# box.net
KiCad netlist of a schematic drawn in EAGLE
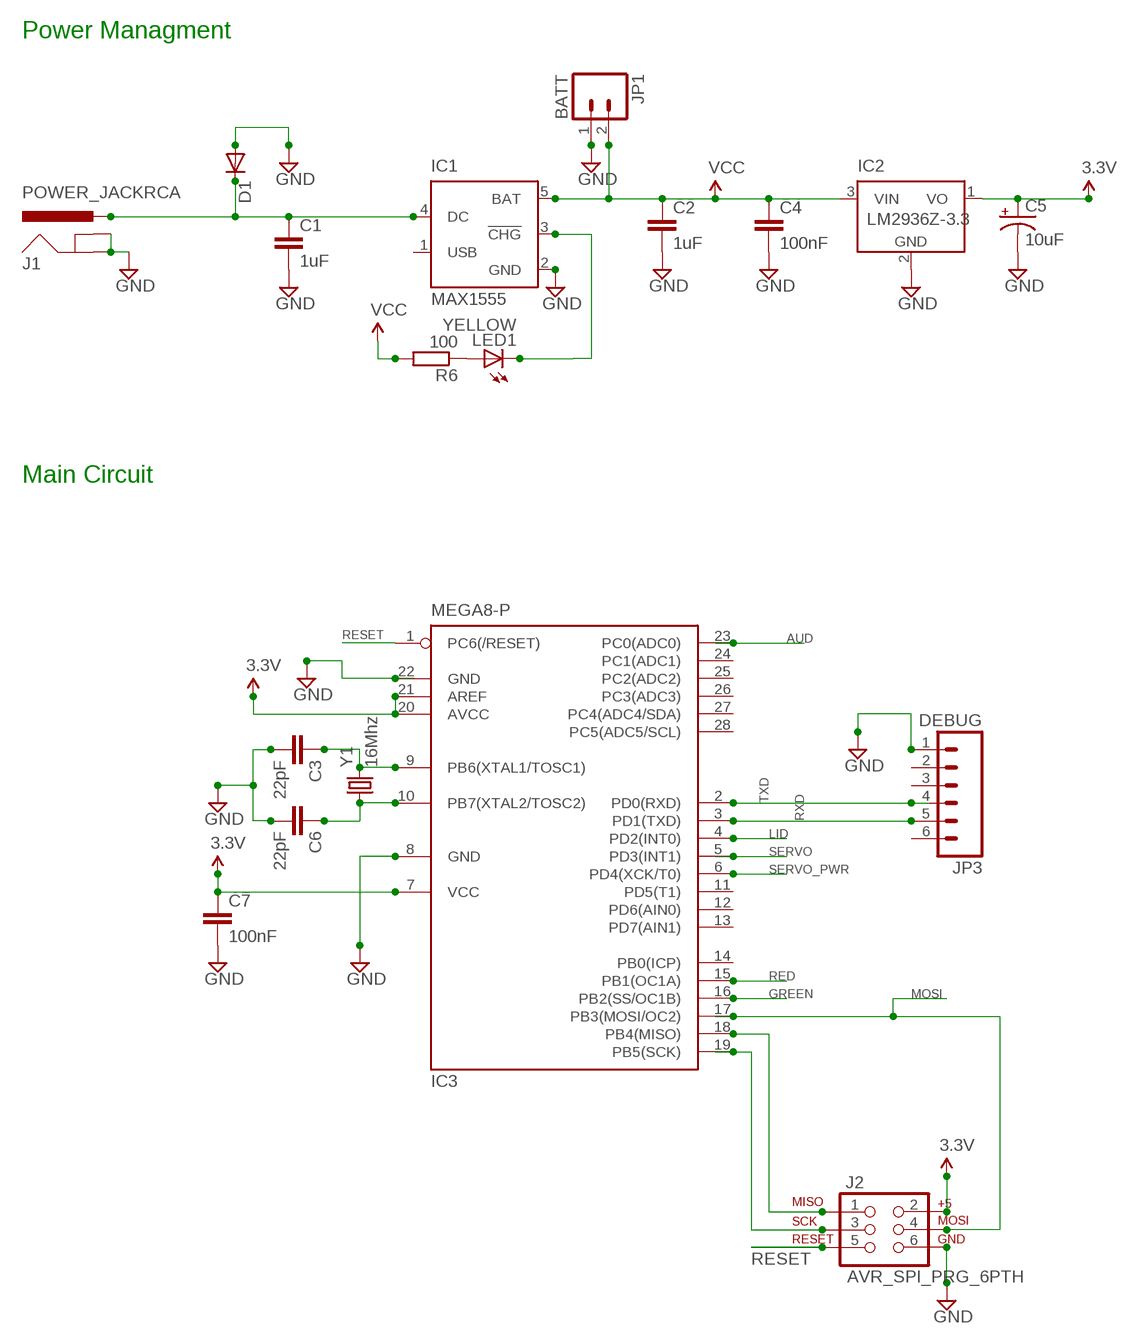
[diagram p0: schematic, sheet 1, part 1 of 2]
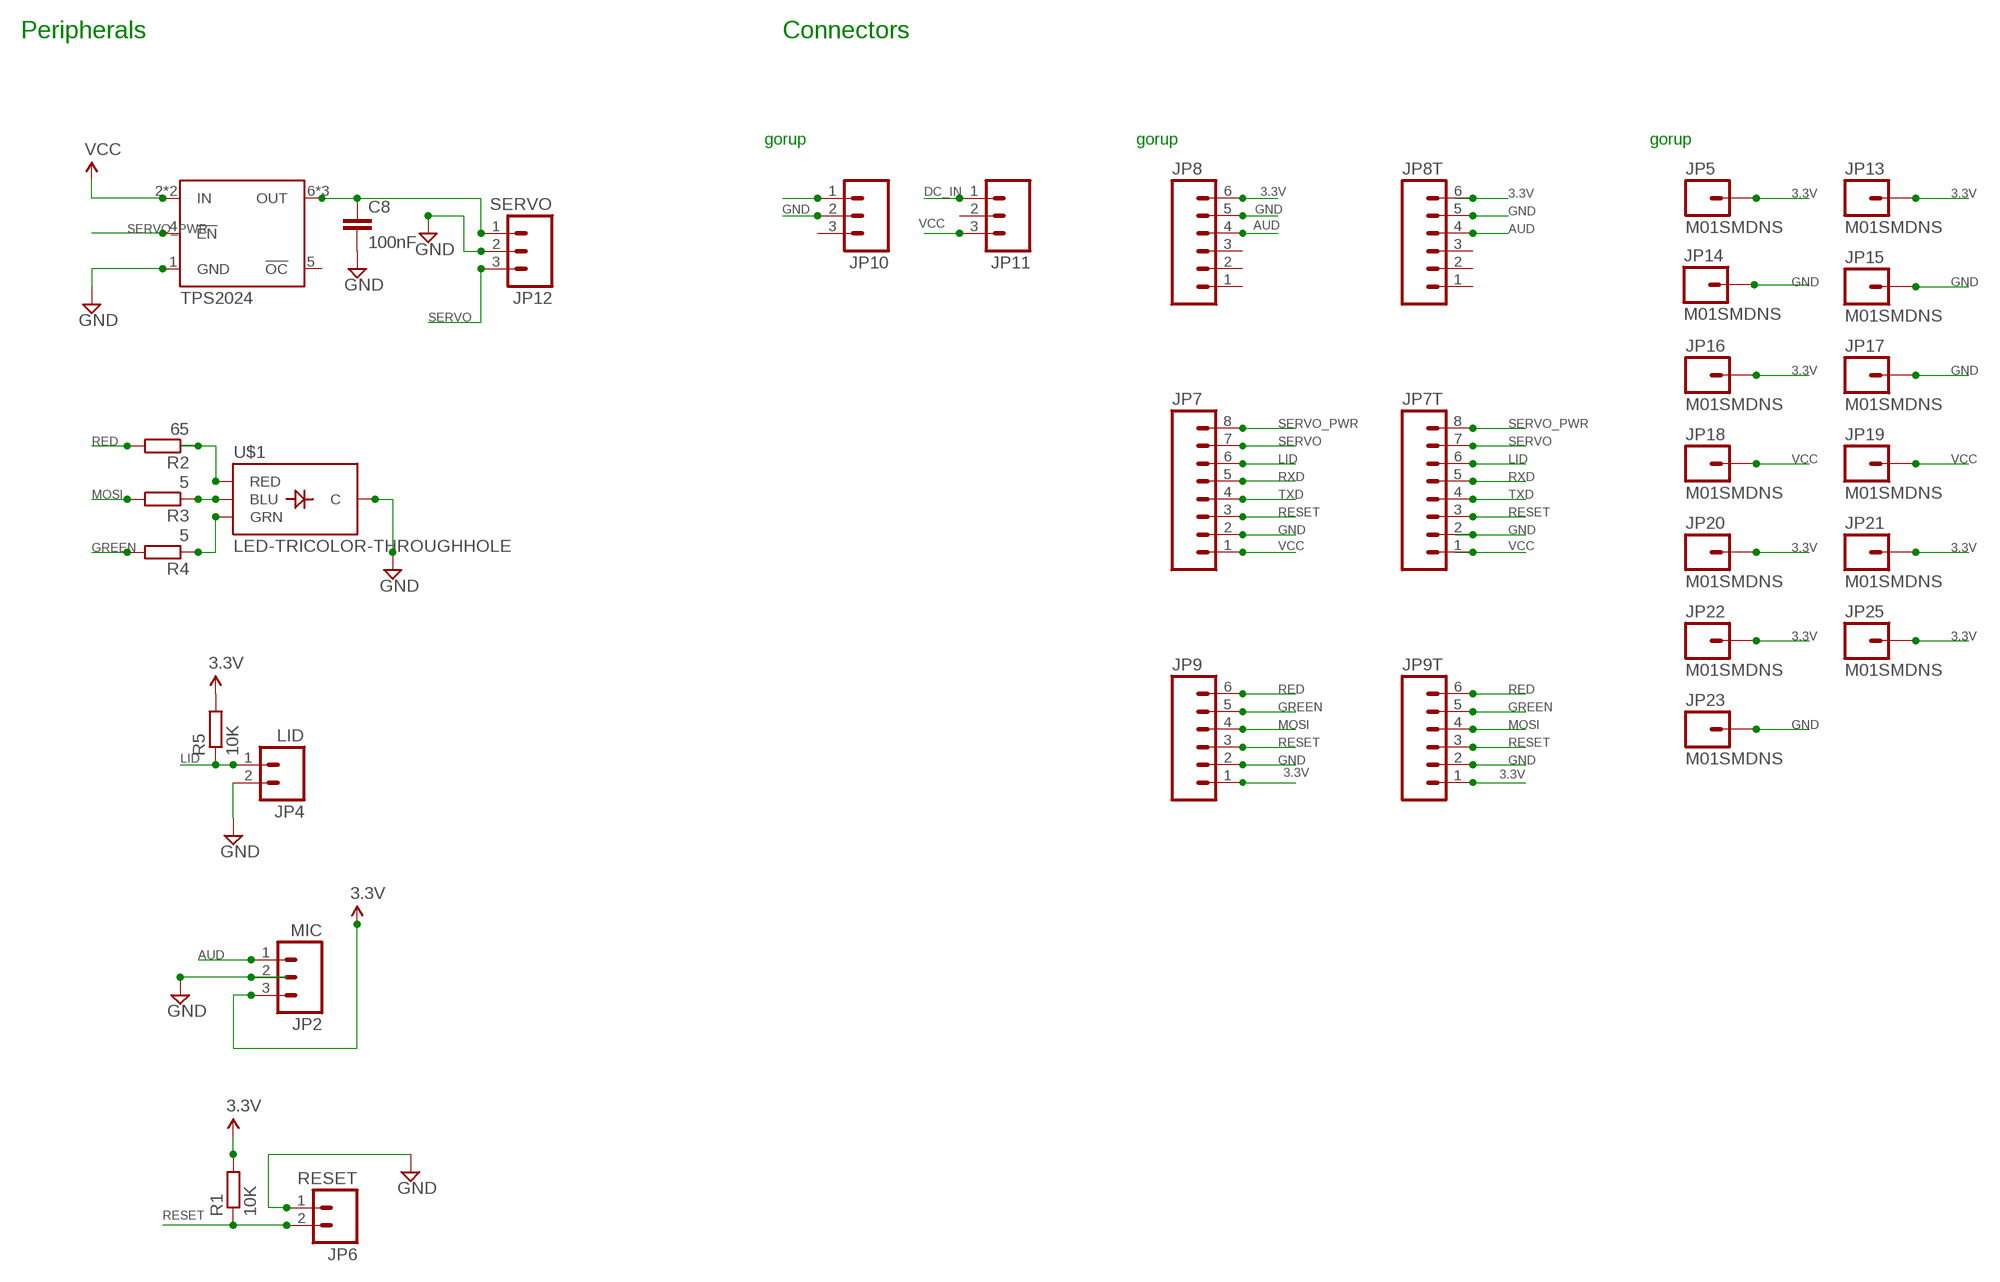
[diagram p1: schematic, sheet 1, part 2 of 2]

(export (version "E")
  (design (tool "Eeschema 10.0.6"))
  (components
    (comp (ref "C1")
      (value "1uF")
      (footprint "eagle-import:AXIAL-5MM")
      (libsource (lib "eagle-import") (part "CAP_"))
    )
    (comp (ref "C2")
      (value "1uF")
      (footprint "eagle-import:AXIAL-5MM")
      (libsource (lib "eagle-import") (part "CAP_"))
    )
    (comp (ref "C3")
      (value "22pF")
      (footprint "eagle-import:C2.5-2")
      (libsource (lib "eagle-import") (part "C2.5/2"))
    )
    (comp (ref "C4")
      (value "100nF")
      (footprint "eagle-import:C5B3.5")
      (libsource (lib "eagle-import") (part "C5/3.5"))
    )
    (comp (ref "C5")
      (value "10uF")
      (footprint "eagle-import:CPOL-RADIAL-10UF-25V")
      (libsource (lib "eagle-import") (part "CAP_POLPTH2"))
    )
    (comp (ref "C6")
      (value "22pF")
      (footprint "eagle-import:C2.5-2")
      (libsource (lib "eagle-import") (part "C2.5/2"))
    )
    (comp (ref "C7")
      (value "100nF")
      (footprint "eagle-import:C5B3.5")
      (libsource (lib "eagle-import") (part "C5/3.5"))
    )
    (comp (ref "C8")
      (value "100nF")
      (footprint "eagle-import:C5B3.5")
      (libsource (lib "eagle-import") (part "C5/3.5"))
    )
    (comp (ref "D1")
      (value "DIODE-D-2.5")
      (footprint "eagle-import:D-2.5")
      (libsource (lib "eagle-import") (part "DIODE-D-2.5"))
    )
    (comp (ref "IC1")
      (value "MAX1555")
      (footprint "eagle-import:SOT23-5L")
      (fields (field (name "MF") "MAXIM") (field (name "MPN") "MAX1555EZK+T"))
      (libsource (lib "eagle-import") (part "MAX1555"))
    )
    (comp (ref "IC2")
      (value "LM2936Z-3.3")
      (footprint "eagle-import:TO92")
      (fields (field (name "MF") "NATIONAL SEMICONDUCTOR") (field (name "MPN") "LM2936Z-3.3/NOPB"))
      (libsource (lib "eagle-import") (part "LM2936?Z-3.3"))
    )
    (comp (ref "IC3")
      (value "MEGA8-P")
      (footprint "eagle-import:DIL28-3")
      (libsource (lib "eagle-import") (part "MEGA8-P"))
    )
    (comp (ref "J1")
      (value "POWER_JACKRCA")
      (footprint "eagle-import:RCA")
      (libsource (lib "eagle-import") (part "POWER_JACKRCA"))
    )
    (comp (ref "J2")
      (value "AVR_SPI_PRG_6PTH")
      (footprint "eagle-import:2X3")
      (libsource (lib "eagle-import") (part "AVR_SPI_PRG_6PTH"))
    )
    (comp (ref "JP1")
      (value "BATT")
      (footprint "eagle-import:JST-2-PTH-NS")
      (libsource (lib "eagle-import") (part "M02-JST-2-PTH-NO_SILK"))
    )
    (comp (ref "JP2")
      (value "MIC")
      (footprint "eagle-import:1X03")
      (libsource (lib "eagle-import") (part "M03PTH"))
    )
    (comp (ref "JP3")
      (value "DEBUG")
      (footprint "eagle-import:1X06")
      (libsource (lib "eagle-import") (part "M06SIP"))
    )
    (comp (ref "JP4")
      (value "LID")
      (footprint "eagle-import:1X02")
      (libsource (lib "eagle-import") (part "M02PTH"))
    )
    (comp (ref "JP5")
      (value "M01SMDNS")
      (footprint "eagle-import:1X01NS")
      (libsource (lib "eagle-import") (part "M01SMDNS"))
    )
    (comp (ref "JP6")
      (value "RESET")
      (footprint "eagle-import:1X02")
      (libsource (lib "eagle-import") (part "M02PTH"))
    )
    (comp (ref "JP7")
      (value "M081X08")
      (footprint "eagle-import:1X08")
      (libsource (lib "eagle-import") (part "M081X08"))
    )
    (comp (ref "JP7T")
      (value "M081X08")
      (footprint "eagle-import:1X08")
      (libsource (lib "eagle-import") (part "M081X08"))
    )
    (comp (ref "JP8")
      (value "M06SIP")
      (footprint "eagle-import:1X06")
      (libsource (lib "eagle-import") (part "M06SIP"))
    )
    (comp (ref "JP8T")
      (value "M06SIP")
      (footprint "eagle-import:1X06")
      (libsource (lib "eagle-import") (part "M06SIP"))
    )
    (comp (ref "JP9")
      (value "M06SIP")
      (footprint "eagle-import:1X06")
      (libsource (lib "eagle-import") (part "M06SIP"))
    )
    (comp (ref "JP9T")
      (value "M06SIP")
      (footprint "eagle-import:1X06")
      (libsource (lib "eagle-import") (part "M06SIP"))
    )
    (comp (ref "JP10")
      (value "M03PTH")
      (footprint "eagle-import:1X03")
      (libsource (lib "eagle-import") (part "M03PTH"))
    )
    (comp (ref "JP11")
      (value "M03PTH")
      (footprint "eagle-import:1X03")
      (libsource (lib "eagle-import") (part "M03PTH"))
    )
    (comp (ref "JP12")
      (value "SERVO")
      (footprint "eagle-import:1X03")
      (libsource (lib "eagle-import") (part "M03PTH"))
    )
    (comp (ref "JP13")
      (value "M01SMDNS")
      (footprint "eagle-import:1X01NS")
      (libsource (lib "eagle-import") (part "M01SMDNS"))
    )
    (comp (ref "JP14")
      (value "M01SMDNS")
      (footprint "eagle-import:1X01NS")
      (libsource (lib "eagle-import") (part "M01SMDNS"))
    )
    (comp (ref "JP15")
      (value "M01SMDNS")
      (footprint "eagle-import:1X01NS")
      (libsource (lib "eagle-import") (part "M01SMDNS"))
    )
    (comp (ref "JP16")
      (value "M01SMDNS")
      (footprint "eagle-import:1X01NS")
      (libsource (lib "eagle-import") (part "M01SMDNS"))
    )
    (comp (ref "JP17")
      (value "M01SMDNS")
      (footprint "eagle-import:1X01NS")
      (libsource (lib "eagle-import") (part "M01SMDNS"))
    )
    (comp (ref "JP18")
      (value "M01SMDNS")
      (footprint "eagle-import:1X01NS")
      (libsource (lib "eagle-import") (part "M01SMDNS"))
    )
    (comp (ref "JP19")
      (value "M01SMDNS")
      (footprint "eagle-import:1X01NS")
      (libsource (lib "eagle-import") (part "M01SMDNS"))
    )
    (comp (ref "JP20")
      (value "M01SMDNS")
      (footprint "eagle-import:1X01NS")
      (libsource (lib "eagle-import") (part "M01SMDNS"))
    )
    (comp (ref "JP21")
      (value "M01SMDNS")
      (footprint "eagle-import:1X01NS")
      (libsource (lib "eagle-import") (part "M01SMDNS"))
    )
    (comp (ref "JP22")
      (value "M01SMDNS")
      (footprint "eagle-import:1X01NS")
      (libsource (lib "eagle-import") (part "M01SMDNS"))
    )
    (comp (ref "JP23")
      (value "M01SMDNS")
      (footprint "eagle-import:1X01NS")
      (libsource (lib "eagle-import") (part "M01SMDNS"))
    )
    (comp (ref "JP25")
      (value "M01SMDNS")
      (footprint "eagle-import:1X01NS")
      (libsource (lib "eagle-import") (part "M01SMDNS"))
    )
    (comp (ref "LED1")
      (value "YELLOW")
      (footprint "eagle-import:LED5MM")
      (libsource (lib "eagle-import") (part "LED5MM"))
    )
    (comp (ref "R1")
      (value "10K")
      (footprint "eagle-import:0207_5V")
      (libsource (lib "eagle-import") (part "R-EU_0207/5V"))
    )
    (comp (ref "R2")
      (value "65")
      (footprint "eagle-import:0207_5V")
      (libsource (lib "eagle-import") (part "R-EU_0207/5V"))
    )
    (comp (ref "R3")
      (value "5")
      (footprint "eagle-import:0207_5V")
      (libsource (lib "eagle-import") (part "R-EU_0207/5V"))
    )
    (comp (ref "R4")
      (value "5")
      (footprint "eagle-import:0207_5V")
      (libsource (lib "eagle-import") (part "R-EU_0207/5V"))
    )
    (comp (ref "R5")
      (value "10K")
      (footprint "eagle-import:0207_5V")
      (libsource (lib "eagle-import") (part "R-EU_0207/5V"))
    )
    (comp (ref "R6")
      (value "100")
      (footprint "eagle-import:0207_5V")
      (libsource (lib "eagle-import") (part "R-EU_0207/5V"))
    )
    (comp (ref "U$1")
      (value "LED-TRICOLOR-THROUGHHOLE")
      (footprint "eagle-import:LED-TRICOLOR-THROUGHHOLE")
      (libsource (lib "eagle-import") (part "LED-TRICOLOR-THROUGHHOLE"))
    )
    (comp (ref "U$2")
      (value "TPS2024")
      (footprint "eagle-import:DIL08-OPTO")
      (libsource (lib "eagle-import") (part "TPS2024"))
    )
    (comp (ref "Y1")
      (value "16Mhz")
      (footprint "eagle-import:HC49US")
      (libsource (lib "eagle-import") (part "CRYSTALHC49US"))
    )
  )
  (nets
    (net (code "1") (name "/AUD") (class "Default")
      (node (ref "IC3") (pin "23") (pinfunction "PC0(ADC0)_23") (pintype "bidirectional"))
      (node (ref "JP2") (pin "1") (pinfunction "1_1") (pintype "passive"))
      (node (ref "JP8") (pin "4") (pinfunction "4_4") (pintype "passive"))
      (node (ref "JP8T") (pin "4") (pinfunction "4_4") (pintype "passive"))
    )
    (net (code "2") (name "/CHG_OUT") (class "Default")
      (node (ref "IC1") (pin "3") (pinfunction "~{CHG}_3") (pintype "output"))
      (node (ref "JP10") (pin "1") (pinfunction "1_1") (pintype "passive"))
      (node (ref "LED1") (pin "K") (pinfunction "C_K") (pintype "passive"))
    )
    (net (code "3") (name "/DC_IN") (class "Default")
      (node (ref "C1") (pin "P$1") (pinfunction "1_P$1") (pintype "passive"))
      (node (ref "D1") (pin "C") (pinfunction "C_C") (pintype "passive"))
      (node (ref "IC1") (pin "4") (pinfunction "DC_4") (pintype "input"))
      (node (ref "J1") (pin "BREAK") (pinfunction "PWR_BREAK") (pintype "bidirectional"))
      (node (ref "JP11") (pin "1") (pinfunction "1_1") (pintype "passive"))
    )
    (net (code "4") (name "/GREEN") (class "Default")
      (node (ref "IC3") (pin "16") (pinfunction "PB2(SS/OC1B)_16") (pintype "bidirectional"))
      (node (ref "JP9") (pin "5") (pinfunction "5_5") (pintype "passive"))
      (node (ref "JP9T") (pin "5") (pinfunction "5_5") (pintype "passive"))
      (node (ref "R4") (pin "2") (pinfunction "2_2") (pintype "passive"))
    )
    (net (code "5") (name "/LID") (class "Default")
      (node (ref "IC3") (pin "4") (pinfunction "PD2(INT0)_4") (pintype "bidirectional"))
      (node (ref "JP4") (pin "1") (pinfunction "1_1") (pintype "passive"))
      (node (ref "JP7") (pin "6") (pinfunction "6_6") (pintype "passive"))
      (node (ref "JP7T") (pin "6") (pinfunction "6_6") (pintype "passive"))
      (node (ref "R5") (pin "1") (pinfunction "1_1") (pintype "passive"))
    )
    (net (code "6") (name "/MOSI") (class "Default")
      (node (ref "IC3") (pin "17") (pinfunction "PB3(MOSI/OC2)_17") (pintype "bidirectional"))
      (node (ref "J2") (pin "4") (pinfunction "4_4") (pintype "passive"))
      (node (ref "JP9") (pin "4") (pinfunction "4_4") (pintype "passive"))
      (node (ref "JP9T") (pin "4") (pinfunction "4_4") (pintype "passive"))
      (node (ref "R3") (pin "2") (pinfunction "2_2") (pintype "passive"))
    )
    (net (code "7") (name "/RED") (class "Default")
      (node (ref "IC3") (pin "15") (pinfunction "PB1(OC1A)_15") (pintype "bidirectional"))
      (node (ref "JP9") (pin "6") (pinfunction "6_6") (pintype "passive"))
      (node (ref "JP9T") (pin "6") (pinfunction "6_6") (pintype "passive"))
      (node (ref "R2") (pin "2") (pinfunction "2_2") (pintype "passive"))
    )
    (net (code "8") (name "/RESET") (class "Default")
      (node (ref "IC3") (pin "1") (pinfunction "PC6(/RESET)_1") (pintype "bidirectional"))
      (node (ref "J2") (pin "5") (pinfunction "5_5") (pintype "passive"))
      (node (ref "JP6") (pin "2") (pinfunction "2_2") (pintype "passive"))
      (node (ref "JP7") (pin "3") (pinfunction "3_3") (pintype "passive"))
      (node (ref "JP7T") (pin "3") (pinfunction "3_3") (pintype "passive"))
      (node (ref "JP9") (pin "3") (pinfunction "3_3") (pintype "passive"))
      (node (ref "JP9T") (pin "3") (pinfunction "3_3") (pintype "passive"))
      (node (ref "R1") (pin "1") (pinfunction "1_1") (pintype "passive"))
    )
    (net (code "9") (name "/RXD") (class "Default")
      (node (ref "IC3") (pin "3") (pinfunction "PD1(TXD)_3") (pintype "bidirectional"))
      (node (ref "JP3") (pin "5") (pinfunction "5_5") (pintype "passive"))
      (node (ref "JP7") (pin "5") (pinfunction "5_5") (pintype "passive"))
      (node (ref "JP7T") (pin "5") (pinfunction "5_5") (pintype "passive"))
    )
    (net (code "10") (name "/SERVO") (class "Default")
      (node (ref "IC3") (pin "5") (pinfunction "PD3(INT1)_5") (pintype "bidirectional"))
      (node (ref "JP12") (pin "3") (pinfunction "3_3") (pintype "passive"))
      (node (ref "JP7") (pin "7") (pinfunction "7_7") (pintype "passive"))
      (node (ref "JP7T") (pin "7") (pinfunction "7_7") (pintype "passive"))
    )
    (net (code "11") (name "/SERVO_PWR") (class "Default")
      (node (ref "IC3") (pin "6") (pinfunction "PD4(XCK/T0)_6") (pintype "bidirectional"))
      (node (ref "JP7") (pin "8") (pinfunction "8_8") (pintype "passive"))
      (node (ref "JP7T") (pin "8") (pinfunction "8_8") (pintype "passive"))
      (node (ref "U$2") (pin "4") (pinfunction "~{EN}_4") (pintype "input"))
    )
    (net (code "12") (name "/TXD") (class "Default")
      (node (ref "IC3") (pin "2") (pinfunction "PD0(RXD)_2") (pintype "bidirectional"))
      (node (ref "JP3") (pin "4") (pinfunction "4_4") (pintype "passive"))
      (node (ref "JP7") (pin "4") (pinfunction "4_4") (pintype "passive"))
      (node (ref "JP7T") (pin "4") (pinfunction "4_4") (pintype "passive"))
    )
    (net (code "13") (name "3.3V") (class "Default")
      (node (ref "C5") (pin "1") (pinfunction "+_1") (pintype "passive"))
      (node (ref "C7") (pin "1") (pinfunction "1_1") (pintype "passive"))
      (node (ref "IC2") (pin "1") (pinfunction "VO_1") (pintype "passive"))
      (node (ref "IC3") (pin "20") (pinfunction "AVCC_20") (pintype "power_in"))
      (node (ref "IC3") (pin "21") (pinfunction "AREF_21") (pintype "passive"))
      (node (ref "IC3") (pin "7") (pinfunction "VCC_7") (pintype "power_in"))
      (node (ref "J2") (pin "2") (pinfunction "2_2") (pintype "passive"))
      (node (ref "JP13") (pin "1") (pinfunction "1_1") (pintype "passive"))
      (node (ref "JP16") (pin "1") (pinfunction "1_1") (pintype "passive"))
      (node (ref "JP2") (pin "3") (pinfunction "3_3") (pintype "passive"))
      (node (ref "JP20") (pin "1") (pinfunction "1_1") (pintype "passive"))
      (node (ref "JP21") (pin "1") (pinfunction "1_1") (pintype "passive"))
      (node (ref "JP22") (pin "1") (pinfunction "1_1") (pintype "passive"))
      (node (ref "JP25") (pin "1") (pinfunction "1_1") (pintype "passive"))
      (node (ref "JP5") (pin "1") (pinfunction "1_1") (pintype "passive"))
      (node (ref "JP8") (pin "6") (pinfunction "6_6") (pintype "passive"))
      (node (ref "JP8T") (pin "6") (pinfunction "6_6") (pintype "passive"))
      (node (ref "JP9") (pin "1") (pinfunction "1_1") (pintype "passive"))
      (node (ref "JP9T") (pin "1") (pinfunction "1_1") (pintype "passive"))
      (node (ref "R1") (pin "2") (pinfunction "2_2") (pintype "passive"))
      (node (ref "R5") (pin "2") (pinfunction "2_2") (pintype "passive"))
    )
    (net (code "14") (name "GND") (class "Default")
      (node (ref "C1") (pin "P$2") (pinfunction "2_P$2") (pintype "passive"))
      (node (ref "C2") (pin "P$2") (pinfunction "2_P$2") (pintype "passive"))
      (node (ref "C3") (pin "2") (pinfunction "2_2") (pintype "passive"))
      (node (ref "C4") (pin "2") (pinfunction "2_2") (pintype "passive"))
      (node (ref "C5") (pin "2") (pinfunction "-_2") (pintype "passive"))
      (node (ref "C6") (pin "2") (pinfunction "2_2") (pintype "passive"))
      (node (ref "C7") (pin "2") (pinfunction "2_2") (pintype "passive"))
      (node (ref "C8") (pin "2") (pinfunction "2_2") (pintype "passive"))
      (node (ref "D1") (pin "A") (pinfunction "A_A") (pintype "passive"))
      (node (ref "IC1") (pin "2") (pinfunction "GND_2") (pintype "power_in"))
      (node (ref "IC2") (pin "2") (pinfunction "GND_2") (pintype "passive"))
      (node (ref "IC3") (pin "22") (pinfunction "GND_22") (pintype "power_in"))
      (node (ref "IC3") (pin "8") (pinfunction "GND_8") (pintype "power_in"))
      (node (ref "J1") (pin "BARREL") (pinfunction "GND_BARREL") (pintype "bidirectional"))
      (node (ref "J1") (pin "SPRING") (pinfunction "GNDBREAK_SPRING") (pintype "bidirectional"))
      (node (ref "J2") (pin "6") (pinfunction "6_6") (pintype "passive"))
      (node (ref "JP1") (pin "1") (pinfunction "1_1") (pintype "passive"))
      (node (ref "JP10") (pin "2") (pinfunction "2_2") (pintype "passive"))
      (node (ref "JP12") (pin "2") (pinfunction "2_2") (pintype "passive"))
      (node (ref "JP14") (pin "1") (pinfunction "1_1") (pintype "passive"))
      (node (ref "JP15") (pin "1") (pinfunction "1_1") (pintype "passive"))
      (node (ref "JP17") (pin "1") (pinfunction "1_1") (pintype "passive"))
      (node (ref "JP2") (pin "2") (pinfunction "2_2") (pintype "passive"))
      (node (ref "JP23") (pin "1") (pinfunction "1_1") (pintype "passive"))
      (node (ref "JP3") (pin "1") (pinfunction "1_1") (pintype "passive"))
      (node (ref "JP4") (pin "2") (pinfunction "2_2") (pintype "passive"))
      (node (ref "JP6") (pin "1") (pinfunction "1_1") (pintype "passive"))
      (node (ref "JP7") (pin "2") (pinfunction "2_2") (pintype "passive"))
      (node (ref "JP7T") (pin "2") (pinfunction "2_2") (pintype "passive"))
      (node (ref "JP8") (pin "5") (pinfunction "5_5") (pintype "passive"))
      (node (ref "JP8T") (pin "5") (pinfunction "5_5") (pintype "passive"))
      (node (ref "JP9") (pin "2") (pinfunction "2_2") (pintype "passive"))
      (node (ref "JP9T") (pin "2") (pinfunction "2_2") (pintype "passive"))
      (node (ref "U$1") (pin "GND") (pinfunction "C_GND") (pintype "bidirectional"))
      (node (ref "U$2") (pin "1") (pinfunction "GND_1") (pintype "power_in"))
    )
    (net (code "15") (name "Net-(C8-Pad1)") (class "Default")
      (node (ref "C8") (pin "1") (pinfunction "1_1") (pintype "passive"))
      (node (ref "JP12") (pin "1") (pinfunction "1_1") (pintype "passive"))
      (node (ref "U$2") (pin "6") (pinfunction "OUT_6") (pintype "output"))
      (node (ref "U$2") (pin "7") (pinfunction "OUT_7") (pintype "output"))
      (node (ref "U$2") (pin "8") (pinfunction "OUT_8") (pintype "output"))
    )
    (net (code "16") (name "Net-(IC3-PB4(MISO))") (class "Default")
      (node (ref "IC3") (pin "18") (pinfunction "PB4(MISO)_18") (pintype "bidirectional"))
      (node (ref "J2") (pin "1") (pinfunction "1_1") (pintype "passive"))
    )
    (net (code "17") (name "Net-(IC3-PB5(SCK))") (class "Default")
      (node (ref "IC3") (pin "19") (pinfunction "PB5(SCK)_19") (pintype "bidirectional"))
      (node (ref "J2") (pin "3") (pinfunction "3_3") (pintype "passive"))
    )
    (net (code "18") (name "Net-(IC3-PB6(XTAL1{slash}TOSC1))") (class "Default")
      (node (ref "C3") (pin "1") (pinfunction "1_1") (pintype "passive"))
      (node (ref "IC3") (pin "9") (pinfunction "PB6(XTAL1/TOSC1)_9") (pintype "bidirectional"))
      (node (ref "Y1") (pin "2") (pinfunction "2_2") (pintype "passive"))
    )
    (net (code "19") (name "Net-(IC3-PB7(XTAL2{slash}TOSC2))") (class "Default")
      (node (ref "C6") (pin "1") (pinfunction "1_1") (pintype "passive"))
      (node (ref "IC3") (pin "10") (pinfunction "PB7(XTAL2/TOSC2)_10") (pintype "bidirectional"))
      (node (ref "Y1") (pin "1") (pinfunction "1_1") (pintype "passive"))
    )
    (net (code "20") (name "Net-(LED1-PadA)") (class "Default")
      (node (ref "LED1") (pin "A") (pinfunction "A_A") (pintype "passive"))
      (node (ref "R6") (pin "1") (pinfunction "1_1") (pintype "passive"))
    )
    (net (code "21") (name "Net-(R2-Pad1)") (class "Default")
      (node (ref "R2") (pin "1") (pinfunction "1_1") (pintype "passive"))
      (node (ref "U$1") (pin "RED") (pinfunction "RED_RED") (pintype "bidirectional"))
    )
    (net (code "22") (name "Net-(R3-Pad1)") (class "Default")
      (node (ref "R3") (pin "1") (pinfunction "1_1") (pintype "passive"))
      (node (ref "U$1") (pin "BLU") (pinfunction "BLU_BLU") (pintype "bidirectional"))
    )
    (net (code "23") (name "Net-(R4-Pad1)") (class "Default")
      (node (ref "R4") (pin "1") (pinfunction "1_1") (pintype "passive"))
      (node (ref "U$1") (pin "GRN") (pinfunction "GRN_GRN") (pintype "bidirectional"))
    )
    (net (code "24") (name "VCC") (class "Default")
      (node (ref "C2") (pin "P$1") (pinfunction "1_P$1") (pintype "passive"))
      (node (ref "C4") (pin "1") (pinfunction "1_1") (pintype "passive"))
      (node (ref "IC1") (pin "5") (pinfunction "BAT_5") (pintype "passive"))
      (node (ref "IC2") (pin "3") (pinfunction "VIN_3") (pintype "input"))
      (node (ref "JP1") (pin "2") (pinfunction "2_2") (pintype "passive"))
      (node (ref "JP11") (pin "3") (pinfunction "3_3") (pintype "passive"))
      (node (ref "JP18") (pin "1") (pinfunction "1_1") (pintype "passive"))
      (node (ref "JP19") (pin "1") (pinfunction "1_1") (pintype "passive"))
      (node (ref "JP7") (pin "1") (pinfunction "1_1") (pintype "passive"))
      (node (ref "JP7T") (pin "1") (pinfunction "1_1") (pintype "passive"))
      (node (ref "R6") (pin "2") (pinfunction "2_2") (pintype "passive"))
      (node (ref "U$2") (pin "2") (pinfunction "IN_2") (pintype "input"))
      (node (ref "U$2") (pin "3") (pinfunction "IN_3") (pintype "input"))
    )
    (net (code "25") (name "unconnected-(IC1-USB-Pad1)") (class "Default")
      (node (ref "IC1") (pin "1") (pinfunction "USB_1") (pintype "input"))
    )
    (net (code "26") (name "unconnected-(IC3-PB0(ICP)-Pad14)") (class "Default")
      (node (ref "IC3") (pin "14") (pinfunction "PB0(ICP)_14") (pintype "bidirectional"))
    )
    (net (code "27") (name "unconnected-(IC3-PC1(ADC1)-Pad24)") (class "Default")
      (node (ref "IC3") (pin "24") (pinfunction "PC1(ADC1)_24") (pintype "bidirectional"))
    )
    (net (code "28") (name "unconnected-(IC3-PC2(ADC2)-Pad25)") (class "Default")
      (node (ref "IC3") (pin "25") (pinfunction "PC2(ADC2)_25") (pintype "bidirectional"))
    )
    (net (code "29") (name "unconnected-(IC3-PC3(ADC3)-Pad26)") (class "Default")
      (node (ref "IC3") (pin "26") (pinfunction "PC3(ADC3)_26") (pintype "bidirectional"))
    )
    (net (code "30") (name "unconnected-(IC3-PC4(ADC4{slash}SDA)-Pad27)") (class "Default")
      (node (ref "IC3") (pin "27") (pinfunction "PC4(ADC4/SDA)_27") (pintype "bidirectional"))
    )
    (net (code "31") (name "unconnected-(IC3-PC5(ADC5{slash}SCL)-Pad28)") (class "Default")
      (node (ref "IC3") (pin "28") (pinfunction "PC5(ADC5/SCL)_28") (pintype "bidirectional"))
    )
    (net (code "32") (name "unconnected-(IC3-PD5(T1)-Pad11)") (class "Default")
      (node (ref "IC3") (pin "11") (pinfunction "PD5(T1)_11") (pintype "bidirectional"))
    )
    (net (code "33") (name "unconnected-(IC3-PD6(AIN0)-Pad12)") (class "Default")
      (node (ref "IC3") (pin "12") (pinfunction "PD6(AIN0)_12") (pintype "bidirectional"))
    )
    (net (code "34") (name "unconnected-(IC3-PD7(AIN1)-Pad13)") (class "Default")
      (node (ref "IC3") (pin "13") (pinfunction "PD7(AIN1)_13") (pintype "bidirectional"))
    )
    (net (code "35") (name "unconnected-(JP3-Pad2)") (class "Default")
      (node (ref "JP3") (pin "2") (pinfunction "2_2") (pintype "passive"))
    )
    (net (code "36") (name "unconnected-(JP3-Pad3)") (class "Default")
      (node (ref "JP3") (pin "3") (pinfunction "3_3") (pintype "passive"))
    )
    (net (code "37") (name "unconnected-(JP3-Pad6)") (class "Default")
      (node (ref "JP3") (pin "6") (pinfunction "6_6") (pintype "passive"))
    )
    (net (code "38") (name "unconnected-(JP8-Pad1)") (class "Default")
      (node (ref "JP8") (pin "1") (pinfunction "1_1") (pintype "passive"))
    )
    (net (code "39") (name "unconnected-(JP8-Pad2)") (class "Default")
      (node (ref "JP8") (pin "2") (pinfunction "2_2") (pintype "passive"))
    )
    (net (code "40") (name "unconnected-(JP8-Pad3)") (class "Default")
      (node (ref "JP8") (pin "3") (pinfunction "3_3") (pintype "passive"))
    )
    (net (code "41") (name "unconnected-(JP8T-Pad1)") (class "Default")
      (node (ref "JP8T") (pin "1") (pinfunction "1_1") (pintype "passive"))
    )
    (net (code "42") (name "unconnected-(JP8T-Pad2)") (class "Default")
      (node (ref "JP8T") (pin "2") (pinfunction "2_2") (pintype "passive"))
    )
    (net (code "43") (name "unconnected-(JP8T-Pad3)") (class "Default")
      (node (ref "JP8T") (pin "3") (pinfunction "3_3") (pintype "passive"))
    )
    (net (code "44") (name "unconnected-(JP10-Pad3)") (class "Default")
      (node (ref "JP10") (pin "3") (pinfunction "3_3") (pintype "passive"))
    )
    (net (code "45") (name "unconnected-(JP11-Pad2)") (class "Default")
      (node (ref "JP11") (pin "2") (pinfunction "2_2") (pintype "passive"))
    )
    (net (code "46") (name "unconnected-(U$2-~{OC}-Pad5)") (class "Default")
      (node (ref "U$2") (pin "5") (pinfunction "~{OC}_5") (pintype "open_collector"))
    )
  )
)
